# picostepsynth.net
KiCad netlist of a schematic drawn in EAGLE
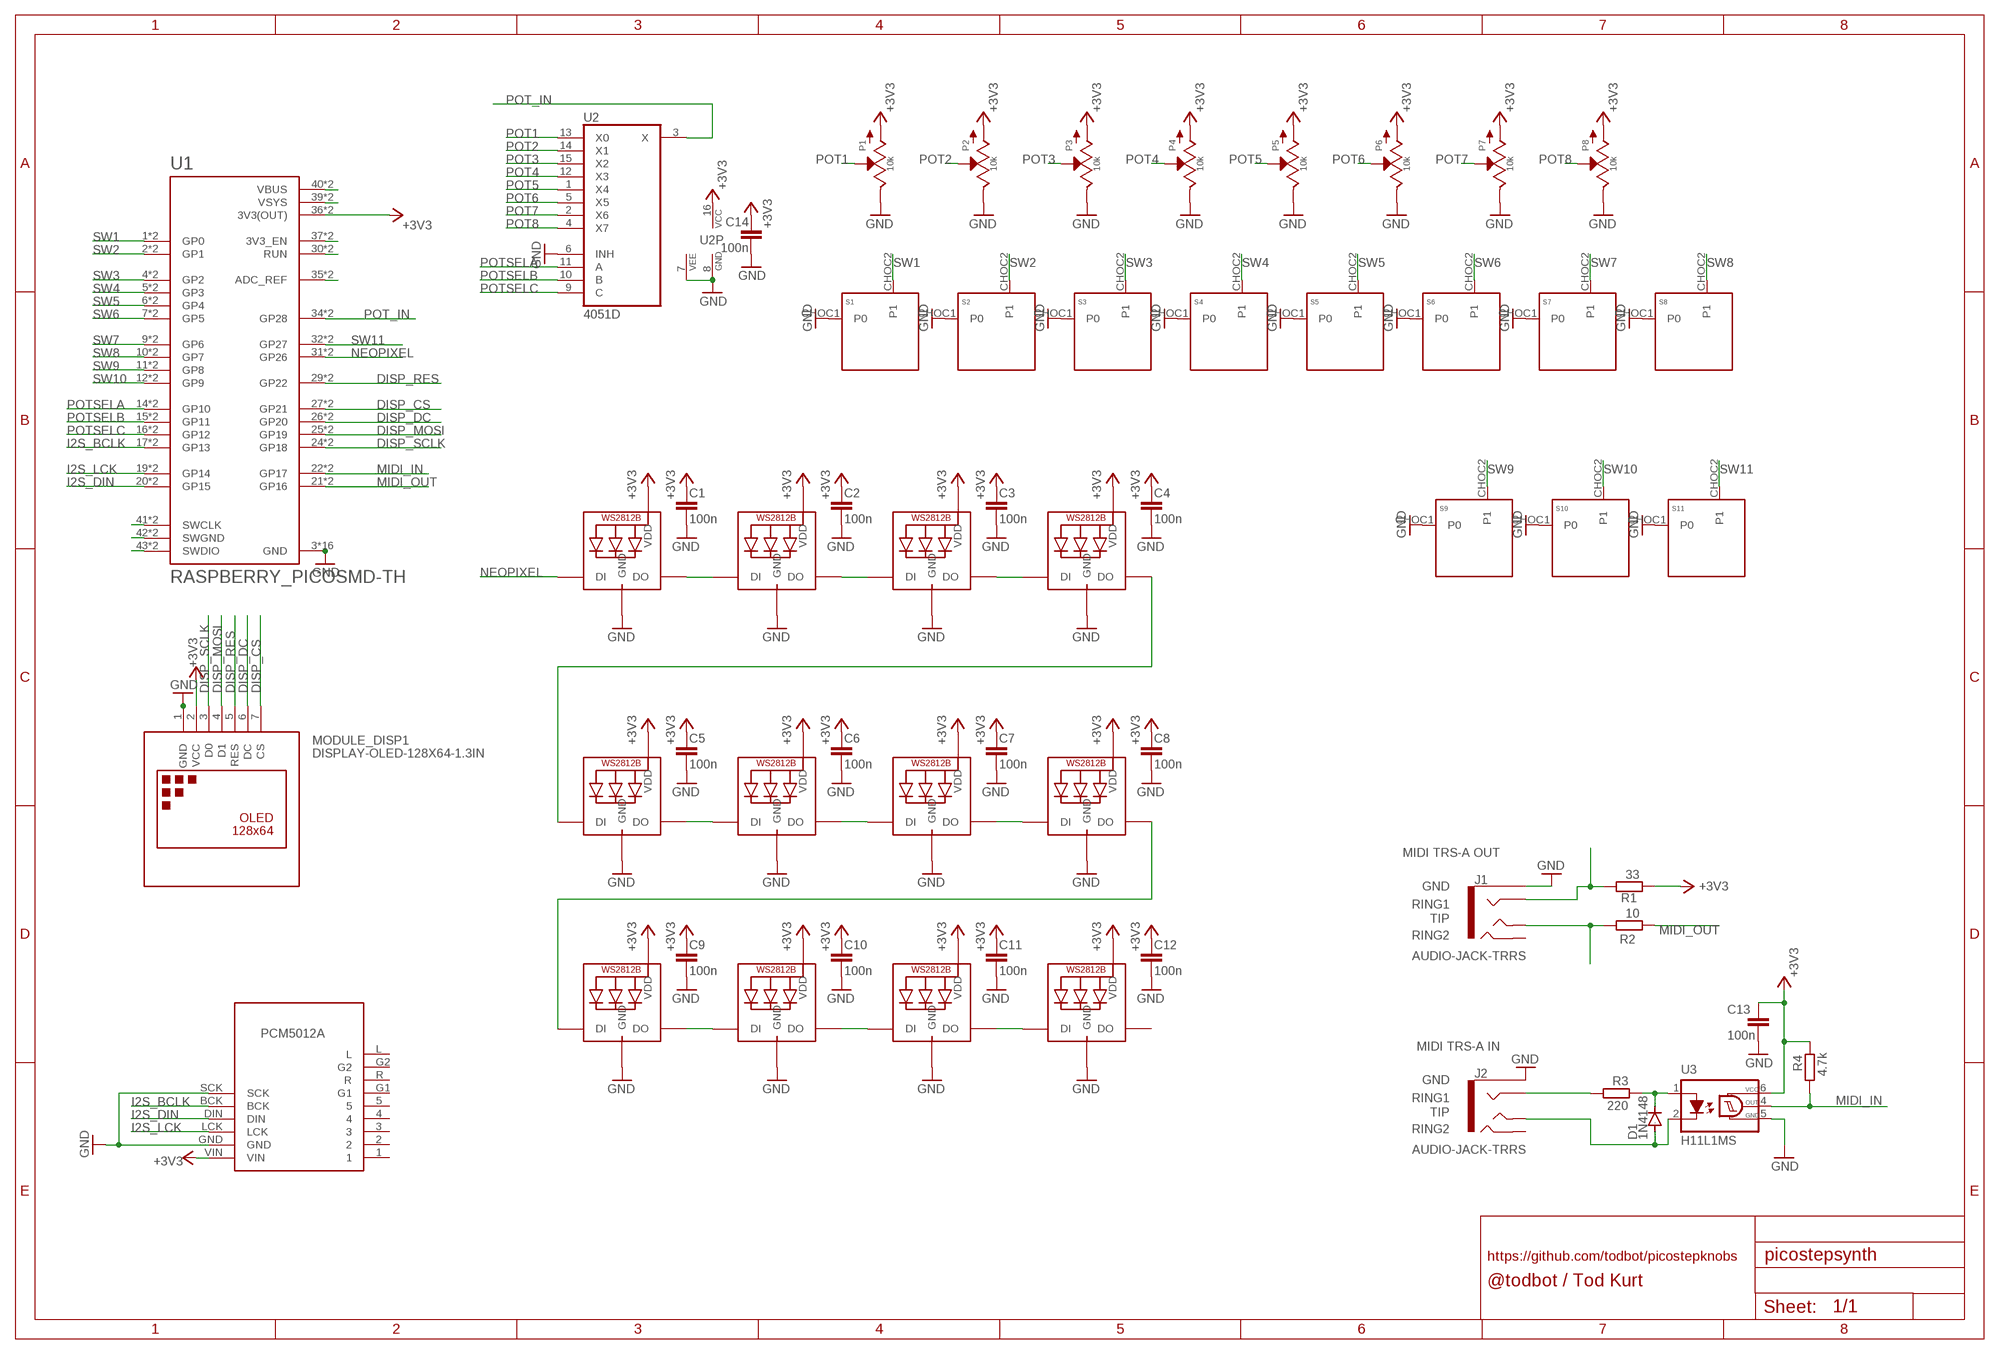
[diagram p0: schematic, sheet 1]

(export (version "E")
  (design (tool "Eeschema 10.0.6"))
  (components
    (comp (ref "C1")
      (value "100n")
      (footprint "eagle-import:C0805")
      (libsource (lib "eagle-import") (part "C-EUC0805"))
    )
    (comp (ref "C2")
      (value "100n")
      (footprint "eagle-import:C0805")
      (libsource (lib "eagle-import") (part "C-EUC0805"))
    )
    (comp (ref "C3")
      (value "100n")
      (footprint "eagle-import:C0805")
      (libsource (lib "eagle-import") (part "C-EUC0805"))
    )
    (comp (ref "C4")
      (value "100n")
      (footprint "eagle-import:C0805")
      (libsource (lib "eagle-import") (part "C-EUC0805"))
    )
    (comp (ref "C5")
      (value "100n")
      (footprint "eagle-import:C0805")
      (libsource (lib "eagle-import") (part "C-EUC0805"))
    )
    (comp (ref "C6")
      (value "100n")
      (footprint "eagle-import:C0805")
      (libsource (lib "eagle-import") (part "C-EUC0805"))
    )
    (comp (ref "C7")
      (value "100n")
      (footprint "eagle-import:C0805")
      (libsource (lib "eagle-import") (part "C-EUC0805"))
    )
    (comp (ref "C8")
      (value "100n")
      (footprint "eagle-import:C0805")
      (libsource (lib "eagle-import") (part "C-EUC0805"))
    )
    (comp (ref "C9")
      (value "100n")
      (footprint "eagle-import:C0805")
      (libsource (lib "eagle-import") (part "C-EUC0805"))
    )
    (comp (ref "C10")
      (value "100n")
      (footprint "eagle-import:C0805")
      (libsource (lib "eagle-import") (part "C-EUC0805"))
    )
    (comp (ref "C11")
      (value "100n")
      (footprint "eagle-import:C0805")
      (libsource (lib "eagle-import") (part "C-EUC0805"))
    )
    (comp (ref "C12")
      (value "100n")
      (footprint "eagle-import:C0805")
      (libsource (lib "eagle-import") (part "C-EUC0805"))
    )
    (comp (ref "C13")
      (value "100n")
      (footprint "eagle-import:C0805")
      (libsource (lib "eagle-import") (part "C-EUC0805"))
    )
    (comp (ref "C14")
      (value "100n")
      (footprint "eagle-import:C0805")
      (libsource (lib "eagle-import") (part "C-EUC0805"))
    )
    (comp (ref "D1")
      (value "1N4148")
      (footprint "eagle-import:SOD123")
      (libsource (lib "eagle-import") (part "DIODE-SOD123"))
    )
    (comp (ref "J1")
      (value "AUDIO-JACK-TRRS")
      (footprint "eagle-import:PJ-320D_SPARKFUN")
      (fields (field (name "MPN") "PJ-320D") (field (name "LCSC") "C431535"))
      (libsource (lib "eagle-import") (part "AUDIO-JACK-TRRS"))
    )
    (comp (ref "J2")
      (value "AUDIO-JACK-TRRS")
      (footprint "eagle-import:PJ-320D_SPARKFUN")
      (fields (field (name "MPN") "PJ-320D"))
      (libsource (lib "eagle-import") (part "AUDIO-JACK-TRRS"))
    )
    (comp (ref "LED1")
      (value "WS2812B5050")
      (footprint "eagle-import:WS2812B")
      (libsource (lib "eagle-import") (part "WS2812B5050"))
    )
    (comp (ref "LED2")
      (value "WS2812B5050")
      (footprint "eagle-import:WS2812B")
      (libsource (lib "eagle-import") (part "WS2812B5050"))
    )
    (comp (ref "LED3")
      (value "WS2812B5050")
      (footprint "eagle-import:WS2812B")
      (libsource (lib "eagle-import") (part "WS2812B5050"))
    )
    (comp (ref "LED4")
      (value "WS2812B5050")
      (footprint "eagle-import:WS2812B")
      (libsource (lib "eagle-import") (part "WS2812B5050"))
    )
    (comp (ref "LED5")
      (value "WS2812B5050")
      (footprint "eagle-import:WS2812B")
      (libsource (lib "eagle-import") (part "WS2812B5050"))
    )
    (comp (ref "LED6")
      (value "WS2812B5050")
      (footprint "eagle-import:WS2812B")
      (libsource (lib "eagle-import") (part "WS2812B5050"))
    )
    (comp (ref "LED7")
      (value "WS2812B5050")
      (footprint "eagle-import:WS2812B")
      (libsource (lib "eagle-import") (part "WS2812B5050"))
    )
    (comp (ref "LED8")
      (value "WS2812B5050")
      (footprint "eagle-import:WS2812B")
      (libsource (lib "eagle-import") (part "WS2812B5050"))
    )
    (comp (ref "LED9")
      (value "WS2812B5050")
      (footprint "eagle-import:WS2812B")
      (libsource (lib "eagle-import") (part "WS2812B5050"))
    )
    (comp (ref "LED10")
      (value "WS2812B5050")
      (footprint "eagle-import:WS2812B")
      (libsource (lib "eagle-import") (part "WS2812B5050"))
    )
    (comp (ref "LED11")
      (value "WS2812B5050")
      (footprint "eagle-import:WS2812B")
      (libsource (lib "eagle-import") (part "WS2812B5050"))
    )
    (comp (ref "LED12")
      (value "WS2812B5050")
      (footprint "eagle-import:WS2812B")
      (libsource (lib "eagle-import") (part "WS2812B5050"))
    )
    (comp (ref "MODULE_DISP1")
      (value "DISPLAY-OLED-128X64-1.3IN")
      (footprint "eagle-import:DISPLAY-OLED-128X64-1.3IN")
      (libsource (lib "eagle-import") (part "DISPLAY-OLED-128X64-1.3IN"))
    )
    (comp (ref "MODULE_PCM5102A")
      (value "I2S_PCM_51XX_SOUNDCARD")
      (footprint "eagle-import:I2S_PCM_5100_SOUNDCARD")
      (libsource (lib "eagle-import") (part "I2S_PCM_51XX_SOUNDCARD"))
    )
    (comp (ref "P1")
      (value "10k")
      (footprint "eagle-import:OG-POTS_ALPS_POT_VERTICAL_WITHBIGKNOB")
      (libsource (lib "eagle-import") (part "POTZEPHPOT_BIGKNOB"))
    )
    (comp (ref "P2")
      (value "10k")
      (footprint "eagle-import:OG-POTS_ALPS_POT_VERTICAL_WITHBIGKNOB")
      (libsource (lib "eagle-import") (part "POTZEPHPOT_BIGKNOB"))
    )
    (comp (ref "P3")
      (value "10k")
      (footprint "eagle-import:OG-POTS_ALPS_POT_VERTICAL_WITHBIGKNOB")
      (libsource (lib "eagle-import") (part "POTZEPHPOT_BIGKNOB"))
    )
    (comp (ref "P4")
      (value "10k")
      (footprint "eagle-import:OG-POTS_ALPS_POT_VERTICAL_WITHBIGKNOB")
      (libsource (lib "eagle-import") (part "POTZEPHPOT_BIGKNOB"))
    )
    (comp (ref "P5")
      (value "10k")
      (footprint "eagle-import:OG-POTS_ALPS_POT_VERTICAL_WITHBIGKNOB")
      (libsource (lib "eagle-import") (part "POTZEPHPOT_BIGKNOB"))
    )
    (comp (ref "P6")
      (value "10k")
      (footprint "eagle-import:OG-POTS_ALPS_POT_VERTICAL_WITHBIGKNOB")
      (libsource (lib "eagle-import") (part "POTZEPHPOT_BIGKNOB"))
    )
    (comp (ref "P7")
      (value "10k")
      (footprint "eagle-import:OG-POTS_ALPS_POT_VERTICAL_WITHBIGKNOB")
      (libsource (lib "eagle-import") (part "POTZEPHPOT_BIGKNOB"))
    )
    (comp (ref "P8")
      (value "10k")
      (footprint "eagle-import:OG-POTS_ALPS_POT_VERTICAL_WITHBIGKNOB")
      (libsource (lib "eagle-import") (part "POTZEPHPOT_BIGKNOB"))
    )
    (comp (ref "R1")
      (value "33")
      (footprint "eagle-import:R0805")
      (libsource (lib "eagle-import") (part "R-EU_R0805"))
    )
    (comp (ref "R2")
      (value "10")
      (footprint "eagle-import:R0805")
      (libsource (lib "eagle-import") (part "R-EU_R0805"))
    )
    (comp (ref "R3")
      (value "220")
      (footprint "eagle-import:R0805")
      (libsource (lib "eagle-import") (part "R-EU_R0805"))
    )
    (comp (ref "R4")
      (value "4.7k")
      (footprint "eagle-import:R0805")
      (libsource (lib "eagle-import") (part "R-EU_R0805"))
    )
    (comp (ref "S1")
      (value "KEYSWITCH-PLAIN-CHOC-1U")
      (footprint "eagle-import:CHOC-1U")
      (libsource (lib "eagle-import") (part "KEYSWITCH-PLAIN-CHOC-1U"))
    )
    (comp (ref "S2")
      (value "KEYSWITCH-PLAIN-CHOC-1U")
      (footprint "eagle-import:CHOC-1U")
      (libsource (lib "eagle-import") (part "KEYSWITCH-PLAIN-CHOC-1U"))
    )
    (comp (ref "S3")
      (value "KEYSWITCH-PLAIN-CHOC-1U")
      (footprint "eagle-import:CHOC-1U")
      (libsource (lib "eagle-import") (part "KEYSWITCH-PLAIN-CHOC-1U"))
    )
    (comp (ref "S4")
      (value "KEYSWITCH-PLAIN-CHOC-1U")
      (footprint "eagle-import:CHOC-1U")
      (libsource (lib "eagle-import") (part "KEYSWITCH-PLAIN-CHOC-1U"))
    )
    (comp (ref "S5")
      (value "KEYSWITCH-PLAIN-CHOC-1U")
      (footprint "eagle-import:CHOC-1U")
      (libsource (lib "eagle-import") (part "KEYSWITCH-PLAIN-CHOC-1U"))
    )
    (comp (ref "S6")
      (value "KEYSWITCH-PLAIN-CHOC-1U")
      (footprint "eagle-import:CHOC-1U")
      (libsource (lib "eagle-import") (part "KEYSWITCH-PLAIN-CHOC-1U"))
    )
    (comp (ref "S7")
      (value "KEYSWITCH-PLAIN-CHOC-1U")
      (footprint "eagle-import:CHOC-1U")
      (libsource (lib "eagle-import") (part "KEYSWITCH-PLAIN-CHOC-1U"))
    )
    (comp (ref "S8")
      (value "KEYSWITCH-PLAIN-CHOC-1U")
      (footprint "eagle-import:CHOC-1U")
      (libsource (lib "eagle-import") (part "KEYSWITCH-PLAIN-CHOC-1U"))
    )
    (comp (ref "S9")
      (value "KEYSWITCH-PLAIN-CHOC-1U")
      (footprint "eagle-import:CHOC-1U")
      (libsource (lib "eagle-import") (part "KEYSWITCH-PLAIN-CHOC-1U"))
    )
    (comp (ref "S10")
      (value "KEYSWITCH-PLAIN-CHOC-1U")
      (footprint "eagle-import:CHOC-1U")
      (libsource (lib "eagle-import") (part "KEYSWITCH-PLAIN-CHOC-1U"))
    )
    (comp (ref "S11")
      (value "KEYSWITCH-PLAIN-CHOC-1U")
      (footprint "eagle-import:CHOC-1U")
      (libsource (lib "eagle-import") (part "KEYSWITCH-PLAIN-CHOC-1U"))
    )
    (comp (ref "U1")
      (value "RASPBERRY_PICOSMD-TH")
      (footprint "eagle-import:PICO-PKG")
      (libsource (lib "eagle-import") (part "RASPBERRY_PICOSMD-TH"))
    )
    (comp (ref "U2")
      (value "4051D")
      (footprint "eagle-import:SO16")
      (libsource (lib "eagle-import") (part "4051D"))
    )
    (comp (ref "U3")
      (value "H11L1MS")
      (footprint "eagle-import:DIL6-SMD")
      (libsource (lib "eagle-import") (part "H11LMS1"))
    )
  )
  (nets
    (net (code "1") (name "+3V3") (class "Default")
      (node (ref "C1") (pin "1") (pinfunction "1_1") (pintype "passive"))
      (node (ref "C10") (pin "1") (pinfunction "1_1") (pintype "passive"))
      (node (ref "C11") (pin "1") (pinfunction "1_1") (pintype "passive"))
      (node (ref "C12") (pin "1") (pinfunction "1_1") (pintype "passive"))
      (node (ref "C13") (pin "1") (pinfunction "1_1") (pintype "passive"))
      (node (ref "C14") (pin "1") (pinfunction "1_1") (pintype "passive"))
      (node (ref "C2") (pin "1") (pinfunction "1_1") (pintype "passive"))
      (node (ref "C3") (pin "1") (pinfunction "1_1") (pintype "passive"))
      (node (ref "C4") (pin "1") (pinfunction "1_1") (pintype "passive"))
      (node (ref "C5") (pin "1") (pinfunction "1_1") (pintype "passive"))
      (node (ref "C6") (pin "1") (pinfunction "1_1") (pintype "passive"))
      (node (ref "C7") (pin "1") (pinfunction "1_1") (pintype "passive"))
      (node (ref "C8") (pin "1") (pinfunction "1_1") (pintype "passive"))
      (node (ref "C9") (pin "1") (pinfunction "1_1") (pintype "passive"))
      (node (ref "LED1") (pin "1-VDD") (pinfunction "VDD_1-VDD") (pintype "power_in"))
      (node (ref "LED10") (pin "1-VDD") (pinfunction "VDD_1-VDD") (pintype "power_in"))
      (node (ref "LED11") (pin "1-VDD") (pinfunction "VDD_1-VDD") (pintype "power_in"))
      (node (ref "LED12") (pin "1-VDD") (pinfunction "VDD_1-VDD") (pintype "power_in"))
      (node (ref "LED2") (pin "1-VDD") (pinfunction "VDD_1-VDD") (pintype "power_in"))
      (node (ref "LED3") (pin "1-VDD") (pinfunction "VDD_1-VDD") (pintype "power_in"))
      (node (ref "LED4") (pin "1-VDD") (pinfunction "VDD_1-VDD") (pintype "power_in"))
      (node (ref "LED5") (pin "1-VDD") (pinfunction "VDD_1-VDD") (pintype "power_in"))
      (node (ref "LED6") (pin "1-VDD") (pinfunction "VDD_1-VDD") (pintype "power_in"))
      (node (ref "LED7") (pin "1-VDD") (pinfunction "VDD_1-VDD") (pintype "power_in"))
      (node (ref "LED8") (pin "1-VDD") (pinfunction "VDD_1-VDD") (pintype "power_in"))
      (node (ref "LED9") (pin "1-VDD") (pinfunction "VDD_1-VDD") (pintype "power_in"))
      (node (ref "MODULE_DISP1") (pin "2") (pinfunction "VCC_2") (pintype "power_in"))
      (node (ref "MODULE_PCM5102A") (pin "VIN") (pinfunction "VIN_VIN") (pintype "bidirectional"))
      (node (ref "P1") (pin "P$3") (pinfunction "A_P$3") (pintype "passive"))
      (node (ref "P2") (pin "P$3") (pinfunction "A_P$3") (pintype "passive"))
      (node (ref "P3") (pin "P$3") (pinfunction "A_P$3") (pintype "passive"))
      (node (ref "P4") (pin "P$3") (pinfunction "A_P$3") (pintype "passive"))
      (node (ref "P5") (pin "P$3") (pinfunction "A_P$3") (pintype "passive"))
      (node (ref "P6") (pin "P$3") (pinfunction "A_P$3") (pintype "passive"))
      (node (ref "P7") (pin "P$3") (pinfunction "A_P$3") (pintype "passive"))
      (node (ref "P8") (pin "P$3") (pinfunction "A_P$3") (pintype "passive"))
      (node (ref "R1") (pin "2") (pinfunction "2_2") (pintype "passive"))
      (node (ref "R4") (pin "1") (pinfunction "1_1") (pintype "passive"))
      (node (ref "U1") (pin "36") (pinfunction "3V3(OUT)_36") (pintype "power_in"))
      (node (ref "U1") (pin "P$36") (pinfunction "3V3(OUT)_P$36") (pintype "power_in"))
      (node (ref "U2") (pin "16") (pinfunction "VCC_16") (pintype "power_in"))
      (node (ref "U3") (pin "6") (pinfunction "VCC_6") (pintype "power_in"))
    )
    (net (code "2") (name "/DISP_CS") (class "Default")
      (node (ref "MODULE_DISP1") (pin "7") (pinfunction "CS_7") (pintype "bidirectional"))
      (node (ref "U1") (pin "27") (pinfunction "GP21_27") (pintype "bidirectional"))
      (node (ref "U1") (pin "P$27") (pinfunction "GP21_P$27") (pintype "bidirectional"))
    )
    (net (code "3") (name "/DISP_DC") (class "Default")
      (node (ref "MODULE_DISP1") (pin "6") (pinfunction "DC_6") (pintype "bidirectional"))
      (node (ref "U1") (pin "26") (pinfunction "GP20_26") (pintype "bidirectional"))
      (node (ref "U1") (pin "P$26") (pinfunction "GP20_P$26") (pintype "bidirectional"))
    )
    (net (code "4") (name "/DISP_MOSI") (class "Default")
      (node (ref "MODULE_DISP1") (pin "4") (pinfunction "D1_4") (pintype "bidirectional"))
      (node (ref "U1") (pin "25") (pinfunction "GP19_25") (pintype "bidirectional"))
      (node (ref "U1") (pin "P$25") (pinfunction "GP19_P$25") (pintype "bidirectional"))
    )
    (net (code "5") (name "/DISP_RES") (class "Default")
      (node (ref "MODULE_DISP1") (pin "5") (pinfunction "RES_5") (pintype "bidirectional"))
      (node (ref "U1") (pin "29") (pinfunction "GP22_29") (pintype "bidirectional"))
      (node (ref "U1") (pin "P$29") (pinfunction "GP22_P$29") (pintype "bidirectional"))
    )
    (net (code "6") (name "/DISP_SCLK") (class "Default")
      (node (ref "MODULE_DISP1") (pin "3") (pinfunction "D0_3") (pintype "bidirectional"))
      (node (ref "U1") (pin "24") (pinfunction "GP18_24") (pintype "bidirectional"))
      (node (ref "U1") (pin "P$24") (pinfunction "GP18_P$24") (pintype "bidirectional"))
    )
    (net (code "7") (name "/I2S_BCLK") (class "Default")
      (node (ref "MODULE_PCM5102A") (pin "BCK") (pinfunction "BCK_BCK") (pintype "bidirectional"))
      (node (ref "U1") (pin "17") (pinfunction "GP13_17") (pintype "bidirectional"))
      (node (ref "U1") (pin "P$17") (pinfunction "GP13_P$17") (pintype "bidirectional"))
    )
    (net (code "8") (name "/I2S_DIN") (class "Default")
      (node (ref "MODULE_PCM5102A") (pin "DIN") (pinfunction "DIN_DIN") (pintype "bidirectional"))
      (node (ref "U1") (pin "20") (pinfunction "GP15_20") (pintype "bidirectional"))
      (node (ref "U1") (pin "P$20") (pinfunction "GP15_P$20") (pintype "bidirectional"))
    )
    (net (code "9") (name "/I2S_LCK") (class "Default")
      (node (ref "MODULE_PCM5102A") (pin "LCK") (pinfunction "LCK_LCK") (pintype "bidirectional"))
      (node (ref "U1") (pin "19") (pinfunction "GP14_19") (pintype "bidirectional"))
      (node (ref "U1") (pin "P$19") (pinfunction "GP14_P$19") (pintype "bidirectional"))
    )
    (net (code "10") (name "/MIDI_IN") (class "Default")
      (node (ref "R4") (pin "2") (pinfunction "2_2") (pintype "passive"))
      (node (ref "U1") (pin "22") (pinfunction "GP17_22") (pintype "bidirectional"))
      (node (ref "U1") (pin "P$22") (pinfunction "GP17_P$22") (pintype "bidirectional"))
      (node (ref "U3") (pin "4") (pinfunction "OUT_4") (pintype "output"))
    )
    (net (code "11") (name "/MIDI_OUT") (class "Default")
      (node (ref "R2") (pin "2") (pinfunction "2_2") (pintype "passive"))
      (node (ref "U1") (pin "21") (pinfunction "GP16_21") (pintype "bidirectional"))
      (node (ref "U1") (pin "P$21") (pinfunction "GP16_P$21") (pintype "bidirectional"))
    )
    (net (code "12") (name "/NEOPIXEL") (class "Default")
      (node (ref "LED1") (pin "4-DIN") (pinfunction "DI_4-DIN") (pintype "input"))
      (node (ref "U1") (pin "31") (pinfunction "GP26_31") (pintype "bidirectional"))
      (node (ref "U1") (pin "P$31") (pinfunction "GP26_P$31") (pintype "bidirectional"))
    )
    (net (code "13") (name "/POT1") (class "Default")
      (node (ref "P1") (pin "P$2") (pinfunction "S_P$2") (pintype "passive"))
      (node (ref "U2") (pin "13") (pinfunction "X0_13") (pintype "bidirectional"))
    )
    (net (code "14") (name "/POT2") (class "Default")
      (node (ref "P2") (pin "P$2") (pinfunction "S_P$2") (pintype "passive"))
      (node (ref "U2") (pin "14") (pinfunction "X1_14") (pintype "bidirectional"))
    )
    (net (code "15") (name "/POT3") (class "Default")
      (node (ref "P3") (pin "P$2") (pinfunction "S_P$2") (pintype "passive"))
      (node (ref "U2") (pin "15") (pinfunction "X2_15") (pintype "bidirectional"))
    )
    (net (code "16") (name "/POT4") (class "Default")
      (node (ref "P4") (pin "P$2") (pinfunction "S_P$2") (pintype "passive"))
      (node (ref "U2") (pin "12") (pinfunction "X3_12") (pintype "bidirectional"))
    )
    (net (code "17") (name "/POT5") (class "Default")
      (node (ref "P5") (pin "P$2") (pinfunction "S_P$2") (pintype "passive"))
      (node (ref "U2") (pin "1") (pinfunction "X4_1") (pintype "bidirectional"))
    )
    (net (code "18") (name "/POT6") (class "Default")
      (node (ref "P6") (pin "P$2") (pinfunction "S_P$2") (pintype "passive"))
      (node (ref "U2") (pin "5") (pinfunction "X5_5") (pintype "bidirectional"))
    )
    (net (code "19") (name "/POT7") (class "Default")
      (node (ref "P7") (pin "P$2") (pinfunction "S_P$2") (pintype "passive"))
      (node (ref "U2") (pin "2") (pinfunction "X6_2") (pintype "bidirectional"))
    )
    (net (code "20") (name "/POT8") (class "Default")
      (node (ref "P8") (pin "P$2") (pinfunction "S_P$2") (pintype "passive"))
      (node (ref "U2") (pin "4") (pinfunction "X7_4") (pintype "bidirectional"))
    )
    (net (code "21") (name "/POTSELA") (class "Default")
      (node (ref "U1") (pin "14") (pinfunction "GP10_14") (pintype "bidirectional"))
      (node (ref "U1") (pin "P$14") (pinfunction "GP10_P$14") (pintype "bidirectional"))
      (node (ref "U2") (pin "11") (pinfunction "A_11") (pintype "input"))
    )
    (net (code "22") (name "/POTSELB") (class "Default")
      (node (ref "U1") (pin "15") (pinfunction "GP11_15") (pintype "bidirectional"))
      (node (ref "U1") (pin "P$15") (pinfunction "GP11_P$15") (pintype "bidirectional"))
      (node (ref "U2") (pin "10") (pinfunction "B_10") (pintype "input"))
    )
    (net (code "23") (name "/POTSELC") (class "Default")
      (node (ref "U1") (pin "16") (pinfunction "GP12_16") (pintype "bidirectional"))
      (node (ref "U1") (pin "P$16") (pinfunction "GP12_P$16") (pintype "bidirectional"))
      (node (ref "U2") (pin "9") (pinfunction "C_9") (pintype "input"))
    )
    (net (code "24") (name "/POT_IN") (class "Default")
      (node (ref "U1") (pin "34") (pinfunction "GP28_34") (pintype "bidirectional"))
      (node (ref "U1") (pin "P$34") (pinfunction "GP28_P$34") (pintype "bidirectional"))
      (node (ref "U2") (pin "3") (pinfunction "X_3") (pintype "bidirectional"))
    )
    (net (code "25") (name "/SW1") (class "Default")
      (node (ref "S1") (pin "CHOC2") (pinfunction "P1_CHOC2") (pintype "bidirectional"))
      (node (ref "U1") (pin "1") (pinfunction "GP0_1") (pintype "bidirectional"))
      (node (ref "U1") (pin "P$1") (pinfunction "GP0_P$1") (pintype "bidirectional"))
    )
    (net (code "26") (name "/SW2") (class "Default")
      (node (ref "S2") (pin "CHOC2") (pinfunction "P1_CHOC2") (pintype "bidirectional"))
      (node (ref "U1") (pin "2") (pinfunction "GP1_2") (pintype "bidirectional"))
      (node (ref "U1") (pin "P$2") (pinfunction "GP1_P$2") (pintype "bidirectional"))
    )
    (net (code "27") (name "/SW3") (class "Default")
      (node (ref "S3") (pin "CHOC2") (pinfunction "P1_CHOC2") (pintype "bidirectional"))
      (node (ref "U1") (pin "4") (pinfunction "GP2_4") (pintype "bidirectional"))
      (node (ref "U1") (pin "P$4") (pinfunction "GP2_P$4") (pintype "bidirectional"))
    )
    (net (code "28") (name "/SW4") (class "Default")
      (node (ref "S4") (pin "CHOC2") (pinfunction "P1_CHOC2") (pintype "bidirectional"))
      (node (ref "U1") (pin "5") (pinfunction "GP3_5") (pintype "bidirectional"))
      (node (ref "U1") (pin "P$5") (pinfunction "GP3_P$5") (pintype "bidirectional"))
    )
    (net (code "29") (name "/SW5") (class "Default")
      (node (ref "S5") (pin "CHOC2") (pinfunction "P1_CHOC2") (pintype "bidirectional"))
      (node (ref "U1") (pin "6") (pinfunction "GP4_6") (pintype "bidirectional"))
      (node (ref "U1") (pin "P$6") (pinfunction "GP4_P$6") (pintype "bidirectional"))
    )
    (net (code "30") (name "/SW6") (class "Default")
      (node (ref "S6") (pin "CHOC2") (pinfunction "P1_CHOC2") (pintype "bidirectional"))
      (node (ref "U1") (pin "7") (pinfunction "GP5_7") (pintype "bidirectional"))
      (node (ref "U1") (pin "P$7") (pinfunction "GP5_P$7") (pintype "bidirectional"))
    )
    (net (code "31") (name "/SW7") (class "Default")
      (node (ref "S7") (pin "CHOC2") (pinfunction "P1_CHOC2") (pintype "bidirectional"))
      (node (ref "U1") (pin "9") (pinfunction "GP6_9") (pintype "bidirectional"))
      (node (ref "U1") (pin "P$9") (pinfunction "GP6_P$9") (pintype "bidirectional"))
    )
    (net (code "32") (name "/SW8") (class "Default")
      (node (ref "S8") (pin "CHOC2") (pinfunction "P1_CHOC2") (pintype "bidirectional"))
      (node (ref "U1") (pin "10") (pinfunction "GP7_10") (pintype "bidirectional"))
      (node (ref "U1") (pin "P$10") (pinfunction "GP7_P$10") (pintype "bidirectional"))
    )
    (net (code "33") (name "/SW9") (class "Default")
      (node (ref "S9") (pin "CHOC2") (pinfunction "P1_CHOC2") (pintype "bidirectional"))
      (node (ref "U1") (pin "11") (pinfunction "GP8_11") (pintype "bidirectional"))
      (node (ref "U1") (pin "P$11") (pinfunction "GP8_P$11") (pintype "bidirectional"))
    )
    (net (code "34") (name "/SW10") (class "Default")
      (node (ref "S10") (pin "CHOC2") (pinfunction "P1_CHOC2") (pintype "bidirectional"))
      (node (ref "U1") (pin "12") (pinfunction "GP9_12") (pintype "bidirectional"))
      (node (ref "U1") (pin "P$12") (pinfunction "GP9_P$12") (pintype "bidirectional"))
    )
    (net (code "35") (name "/SW11") (class "Default")
      (node (ref "S11") (pin "CHOC2") (pinfunction "P1_CHOC2") (pintype "bidirectional"))
      (node (ref "U1") (pin "32") (pinfunction "GP27_32") (pintype "bidirectional"))
      (node (ref "U1") (pin "P$32") (pinfunction "GP27_P$32") (pintype "bidirectional"))
    )
    (net (code "36") (name "GND") (class "Default")
      (node (ref "C1") (pin "2") (pinfunction "2_2") (pintype "passive"))
      (node (ref "C10") (pin "2") (pinfunction "2_2") (pintype "passive"))
      (node (ref "C11") (pin "2") (pinfunction "2_2") (pintype "passive"))
      (node (ref "C12") (pin "2") (pinfunction "2_2") (pintype "passive"))
      (node (ref "C13") (pin "2") (pinfunction "2_2") (pintype "passive"))
      (node (ref "C14") (pin "2") (pinfunction "2_2") (pintype "passive"))
      (node (ref "C2") (pin "2") (pinfunction "2_2") (pintype "passive"))
      (node (ref "C3") (pin "2") (pinfunction "2_2") (pintype "passive"))
      (node (ref "C4") (pin "2") (pinfunction "2_2") (pintype "passive"))
      (node (ref "C5") (pin "2") (pinfunction "2_2") (pintype "passive"))
      (node (ref "C6") (pin "2") (pinfunction "2_2") (pintype "passive"))
      (node (ref "C7") (pin "2") (pinfunction "2_2") (pintype "passive"))
      (node (ref "C8") (pin "2") (pinfunction "2_2") (pintype "passive"))
      (node (ref "C9") (pin "2") (pinfunction "2_2") (pintype "passive"))
      (node (ref "J1") (pin "EARTH") (pinfunction "EARTH_EARTH") (pintype "bidirectional"))
      (node (ref "J2") (pin "EARTH") (pinfunction "EARTH_EARTH") (pintype "bidirectional"))
      (node (ref "LED1") (pin "3-GND") (pinfunction "GND_3-GND") (pintype "power_in"))
      (node (ref "LED10") (pin "3-GND") (pinfunction "GND_3-GND") (pintype "power_in"))
      (node (ref "LED11") (pin "3-GND") (pinfunction "GND_3-GND") (pintype "power_in"))
      (node (ref "LED12") (pin "3-GND") (pinfunction "GND_3-GND") (pintype "power_in"))
      (node (ref "LED2") (pin "3-GND") (pinfunction "GND_3-GND") (pintype "power_in"))
      (node (ref "LED3") (pin "3-GND") (pinfunction "GND_3-GND") (pintype "power_in"))
      (node (ref "LED4") (pin "3-GND") (pinfunction "GND_3-GND") (pintype "power_in"))
      (node (ref "LED5") (pin "3-GND") (pinfunction "GND_3-GND") (pintype "power_in"))
      (node (ref "LED6") (pin "3-GND") (pinfunction "GND_3-GND") (pintype "power_in"))
      (node (ref "LED7") (pin "3-GND") (pinfunction "GND_3-GND") (pintype "power_in"))
      (node (ref "LED8") (pin "3-GND") (pinfunction "GND_3-GND") (pintype "power_in"))
      (node (ref "LED9") (pin "3-GND") (pinfunction "GND_3-GND") (pintype "power_in"))
      (node (ref "MODULE_DISP1") (pin "1") (pinfunction "GND_1") (pintype "power_in"))
      (node (ref "MODULE_PCM5102A") (pin "GND") (pinfunction "GND_GND") (pintype "bidirectional"))
      (node (ref "MODULE_PCM5102A") (pin "SCK") (pinfunction "SCK_SCK") (pintype "bidirectional"))
      (node (ref "P1") (pin "P$1") (pinfunction "E_P$1") (pintype "passive"))
      (node (ref "P2") (pin "P$1") (pinfunction "E_P$1") (pintype "passive"))
      (node (ref "P3") (pin "P$1") (pinfunction "E_P$1") (pintype "passive"))
      (node (ref "P4") (pin "P$1") (pinfunction "E_P$1") (pintype "passive"))
      (node (ref "P5") (pin "P$1") (pinfunction "E_P$1") (pintype "passive"))
      (node (ref "P6") (pin "P$1") (pinfunction "E_P$1") (pintype "passive"))
      (node (ref "P7") (pin "P$1") (pinfunction "E_P$1") (pintype "passive"))
      (node (ref "P8") (pin "P$1") (pinfunction "E_P$1") (pintype "passive"))
      (node (ref "S1") (pin "CHOC1") (pinfunction "P0_CHOC1") (pintype "bidirectional"))
      (node (ref "S10") (pin "CHOC1") (pinfunction "P0_CHOC1") (pintype "bidirectional"))
      (node (ref "S11") (pin "CHOC1") (pinfunction "P0_CHOC1") (pintype "bidirectional"))
      (node (ref "S2") (pin "CHOC1") (pinfunction "P0_CHOC1") (pintype "bidirectional"))
      (node (ref "S3") (pin "CHOC1") (pinfunction "P0_CHOC1") (pintype "bidirectional"))
      (node (ref "S4") (pin "CHOC1") (pinfunction "P0_CHOC1") (pintype "bidirectional"))
      (node (ref "S5") (pin "CHOC1") (pinfunction "P0_CHOC1") (pintype "bidirectional"))
      (node (ref "S6") (pin "CHOC1") (pinfunction "P0_CHOC1") (pintype "bidirectional"))
      (node (ref "S7") (pin "CHOC1") (pinfunction "P0_CHOC1") (pintype "bidirectional"))
      (node (ref "S8") (pin "CHOC1") (pinfunction "P0_CHOC1") (pintype "bidirectional"))
      (node (ref "S9") (pin "CHOC1") (pinfunction "P0_CHOC1") (pintype "bidirectional"))
      (node (ref "U1") (pin "13") (pinfunction "GND_13") (pintype "power_in"))
      (node (ref "U1") (pin "18") (pinfunction "GND_18") (pintype "power_in"))
      (node (ref "U1") (pin "23") (pinfunction "GND_23") (pintype "power_in"))
      (node (ref "U1") (pin "28") (pinfunction "GND_28") (pintype "power_in"))
      (node (ref "U1") (pin "3") (pinfunction "GND_3") (pintype "power_in"))
      (node (ref "U1") (pin "33") (pinfunction "GND_33") (pintype "power_in"))
      (node (ref "U1") (pin "38") (pinfunction "GND_38") (pintype "power_in"))
      (node (ref "U1") (pin "8") (pinfunction "GND_8") (pintype "power_in"))
      (node (ref "U1") (pin "P$13") (pinfunction "GND_P$13") (pintype "power_in"))
      (node (ref "U1") (pin "P$18") (pinfunction "GND_P$18") (pintype "power_in"))
      (node (ref "U1") (pin "P$23") (pinfunction "GND_P$23") (pintype "power_in"))
      (node (ref "U1") (pin "P$28") (pinfunction "GND_P$28") (pintype "power_in"))
      (node (ref "U1") (pin "P$3") (pinfunction "GND_P$3") (pintype "power_in"))
      (node (ref "U1") (pin "P$33") (pinfunction "GND_P$33") (pintype "power_in"))
      (node (ref "U1") (pin "P$38") (pinfunction "GND_P$38") (pintype "power_in"))
      (node (ref "U1") (pin "P$8") (pinfunction "GND_P$8") (pintype "power_in"))
      (node (ref "U2") (pin "6") (pinfunction "INH_6") (pintype "input"))
      (node (ref "U2") (pin "7") (pinfunction "VEE_7") (pintype "power_in"))
      (node (ref "U2") (pin "8") (pinfunction "GND_8") (pintype "power_in"))
      (node (ref "U3") (pin "5") (pinfunction "GND_5") (pintype "power_in"))
    )
    (net (code "37") (name "Net-(J1-PadRING1)") (class "Default")
      (node (ref "J1") (pin "RING1") (pinfunction "RING1_RING1") (pintype "bidirectional"))
      (node (ref "R1") (pin "1") (pinfunction "1_1") (pintype "passive"))
    )
    (net (code "38") (name "Net-(J1-PadTIP)") (class "Default")
      (node (ref "J1") (pin "TIP") (pinfunction "TIP_TIP") (pintype "bidirectional"))
      (node (ref "R2") (pin "1") (pinfunction "1_1") (pintype "passive"))
    )
    (net (code "39") (name "Net-(J2-PadRING1)") (class "Default")
      (node (ref "J2") (pin "RING1") (pinfunction "RING1_RING1") (pintype "bidirectional"))
      (node (ref "R3") (pin "2") (pinfunction "2_2") (pintype "passive"))
    )
    (net (code "40") (name "Net-(LED1-DO)") (class "Default")
      (node (ref "LED1") (pin "2-DOUT") (pinfunction "DO_2-DOUT") (pintype "output"))
      (node (ref "LED2") (pin "4-DIN") (pinfunction "DI_4-DIN") (pintype "input"))
    )
    (net (code "41") (name "Net-(LED2-DO)") (class "Default")
      (node (ref "LED2") (pin "2-DOUT") (pinfunction "DO_2-DOUT") (pintype "output"))
      (node (ref "LED3") (pin "4-DIN") (pinfunction "DI_4-DIN") (pintype "input"))
    )
    (net (code "42") (name "Net-(LED3-DO)") (class "Default")
      (node (ref "LED3") (pin "2-DOUT") (pinfunction "DO_2-DOUT") (pintype "output"))
      (node (ref "LED4") (pin "4-DIN") (pinfunction "DI_4-DIN") (pintype "input"))
    )
    (net (code "43") (name "Net-(LED4-DO)") (class "Default")
      (node (ref "LED4") (pin "2-DOUT") (pinfunction "DO_2-DOUT") (pintype "output"))
      (node (ref "LED5") (pin "4-DIN") (pinfunction "DI_4-DIN") (pintype "input"))
    )
    (net (code "44") (name "Net-(LED5-DO)") (class "Default")
      (node (ref "LED5") (pin "2-DOUT") (pinfunction "DO_2-DOUT") (pintype "output"))
      (node (ref "LED6") (pin "4-DIN") (pinfunction "DI_4-DIN") (pintype "input"))
    )
    (net (code "45") (name "Net-(LED6-DO)") (class "Default")
      (node (ref "LED6") (pin "2-DOUT") (pinfunction "DO_2-DOUT") (pintype "output"))
      (node (ref "LED7") (pin "4-DIN") (pinfunction "DI_4-DIN") (pintype "input"))
    )
    (net (code "46") (name "Net-(LED7-DO)") (class "Default")
      (node (ref "LED7") (pin "2-DOUT") (pinfunction "DO_2-DOUT") (pintype "output"))
      (node (ref "LED8") (pin "4-DIN") (pinfunction "DI_4-DIN") (pintype "input"))
    )
    (net (code "47") (name "Net-(LED8-DO)") (class "Default")
      (node (ref "LED8") (pin "2-DOUT") (pinfunction "DO_2-DOUT") (pintype "output"))
      (node (ref "LED9") (pin "4-DIN") (pinfunction "DI_4-DIN") (pintype "input"))
    )
    (net (code "48") (name "Net-(LED10-DI)") (class "Default")
      (node (ref "LED10") (pin "4-DIN") (pinfunction "DI_4-DIN") (pintype "input"))
      (node (ref "LED9") (pin "2-DOUT") (pinfunction "DO_2-DOUT") (pintype "output"))
    )
    (net (code "49") (name "Net-(LED10-DO)") (class "Default")
      (node (ref "LED10") (pin "2-DOUT") (pinfunction "DO_2-DOUT") (pintype "output"))
      (node (ref "LED11") (pin "4-DIN") (pinfunction "DI_4-DIN") (pintype "input"))
    )
    (net (code "50") (name "Net-(LED11-DO)") (class "Default")
      (node (ref "LED11") (pin "2-DOUT") (pinfunction "DO_2-DOUT") (pintype "output"))
      (node (ref "LED12") (pin "4-DIN") (pinfunction "DI_4-DIN") (pintype "input"))
    )
    (net (code "51") (name "Net-(U1-3V3_EN-Pad37)") (class "Default")
      (node (ref "U1") (pin "37") (pinfunction "3V3_EN_37") (pintype "input"))
      (node (ref "U1") (pin "P$37") (pinfunction "3V3_EN_P$37") (pintype "input"))
    )
    (net (code "52") (name "Net-(U1-ADC_REF-Pad35)") (class "Default")
      (node (ref "U1") (pin "35") (pinfunction "ADC_REF_35") (pintype "input"))
      (node (ref "U1") (pin "P$35") (pinfunction "ADC_REF_P$35") (pintype "input"))
    )
    (net (code "53") (name "Net-(U1-RUN-Pad30)") (class "Default")
      (node (ref "U1") (pin "30") (pinfunction "RUN_30") (pintype "input"))
      (node (ref "U1") (pin "P$30") (pinfunction "RUN_P$30") (pintype "input"))
    )
    (net (code "54") (name "Net-(U1-SWCLK-Pad41)") (class "Default")
      (node (ref "U1") (pin "41") (pinfunction "SWCLK_41") (pintype "input"))
      (node (ref "U1") (pin "P$41") (pinfunction "SWCLK_P$41") (pintype "input"))
    )
    (net (code "55") (name "Net-(U1-SWDIO-Pad43)") (class "Default")
      (node (ref "U1") (pin "43") (pinfunction "SWDIO_43") (pintype "bidirectional"))
      (node (ref "U1") (pin "P$43") (pinfunction "SWDIO_P$43") (pintype "bidirectional"))
    )
    (net (code "56") (name "Net-(U1-SWGND-Pad42)") (class "Default")
      (node (ref "U1") (pin "42") (pinfunction "SWGND_42") (pintype "power_in"))
      (node (ref "U1") (pin "P$42") (pinfunction "SWGND_P$42") (pintype "power_in"))
    )
    (net (code "57") (name "Net-(U1-VBUS-Pad40)") (class "Default")
      (node (ref "U1") (pin "40") (pinfunction "VBUS_40") (pintype "power_in"))
      (node (ref "U1") (pin "P$40") (pinfunction "VBUS_P$40") (pintype "power_in"))
    )
    (net (code "58") (name "Net-(U1-VSYS-Pad39)") (class "Default")
      (node (ref "U1") (pin "39") (pinfunction "VSYS_39") (pintype "power_in"))
      (node (ref "U1") (pin "P$39") (pinfunction "VSYS_P$39") (pintype "power_in"))
    )
    (net (code "59") (name "Net-(U3-A)") (class "Default")
      (node (ref "D1") (pin "C") (pinfunction "C_C") (pintype "passive"))
      (node (ref "R3") (pin "1") (pinfunction "1_1") (pintype "passive"))
      (node (ref "U3") (pin "1") (pinfunction "A_1") (pintype "passive"))
    )
    (net (code "60") (name "Net-(U3-C)") (class "Default")
      (node (ref "D1") (pin "A") (pinfunction "A_A") (pintype "passive"))
      (node (ref "J2") (pin "TIP") (pinfunction "TIP_TIP") (pintype "bidirectional"))
      (node (ref "U3") (pin "2") (pinfunction "C_2") (pintype "passive"))
    )
    (net (code "61") (name "unconnected-(J1-PadRING2)") (class "Default")
      (node (ref "J1") (pin "RING2") (pinfunction "RING2_RING2") (pintype "bidirectional"))
    )
    (net (code "62") (name "unconnected-(J2-PadRING2)") (class "Default")
      (node (ref "J2") (pin "RING2") (pinfunction "RING2_RING2") (pintype "bidirectional"))
    )
    (net (code "63") (name "unconnected-(LED12-DO-Pad2-DOUT)") (class "Default")
      (node (ref "LED12") (pin "2-DOUT") (pinfunction "DO_2-DOUT") (pintype "output"))
    )
    (net (code "64") (name "unconnected-(MODULE_PCM5102A-Pad1)") (class "Default")
      (node (ref "MODULE_PCM5102A") (pin "1") (pinfunction "1_1") (pintype "bidirectional"))
    )
    (net (code "65") (name "unconnected-(MODULE_PCM5102A-Pad2)") (class "Default")
      (node (ref "MODULE_PCM5102A") (pin "2") (pinfunction "2_2") (pintype "bidirectional"))
    )
    (net (code "66") (name "unconnected-(MODULE_PCM5102A-Pad3)") (class "Default")
      (node (ref "MODULE_PCM5102A") (pin "3") (pinfunction "3_3") (pintype "bidirectional"))
    )
    (net (code "67") (name "unconnected-(MODULE_PCM5102A-Pad4)") (class "Default")
      (node (ref "MODULE_PCM5102A") (pin "4") (pinfunction "4_4") (pintype "bidirectional"))
    )
    (net (code "68") (name "unconnected-(MODULE_PCM5102A-Pad5)") (class "Default")
      (node (ref "MODULE_PCM5102A") (pin "5") (pinfunction "5_5") (pintype "bidirectional"))
    )
    (net (code "69") (name "unconnected-(MODULE_PCM5102A-PadG1)") (class "Default")
      (node (ref "MODULE_PCM5102A") (pin "G1") (pinfunction "G1_G1") (pintype "bidirectional"))
    )
    (net (code "70") (name "unconnected-(MODULE_PCM5102A-PadG2)") (class "Default")
      (node (ref "MODULE_PCM5102A") (pin "G2") (pinfunction "G2_G2") (pintype "bidirectional"))
    )
    (net (code "71") (name "unconnected-(MODULE_PCM5102A-PadL)") (class "Default")
      (node (ref "MODULE_PCM5102A") (pin "L") (pinfunction "L_L") (pintype "bidirectional"))
    )
    (net (code "72") (name "unconnected-(MODULE_PCM5102A-PadR)") (class "Default")
      (node (ref "MODULE_PCM5102A") (pin "R") (pinfunction "R_R") (pintype "bidirectional"))
    )
  )
)
